# BI4.net
KiCad netlist of a schematic drawn in Altium Designer
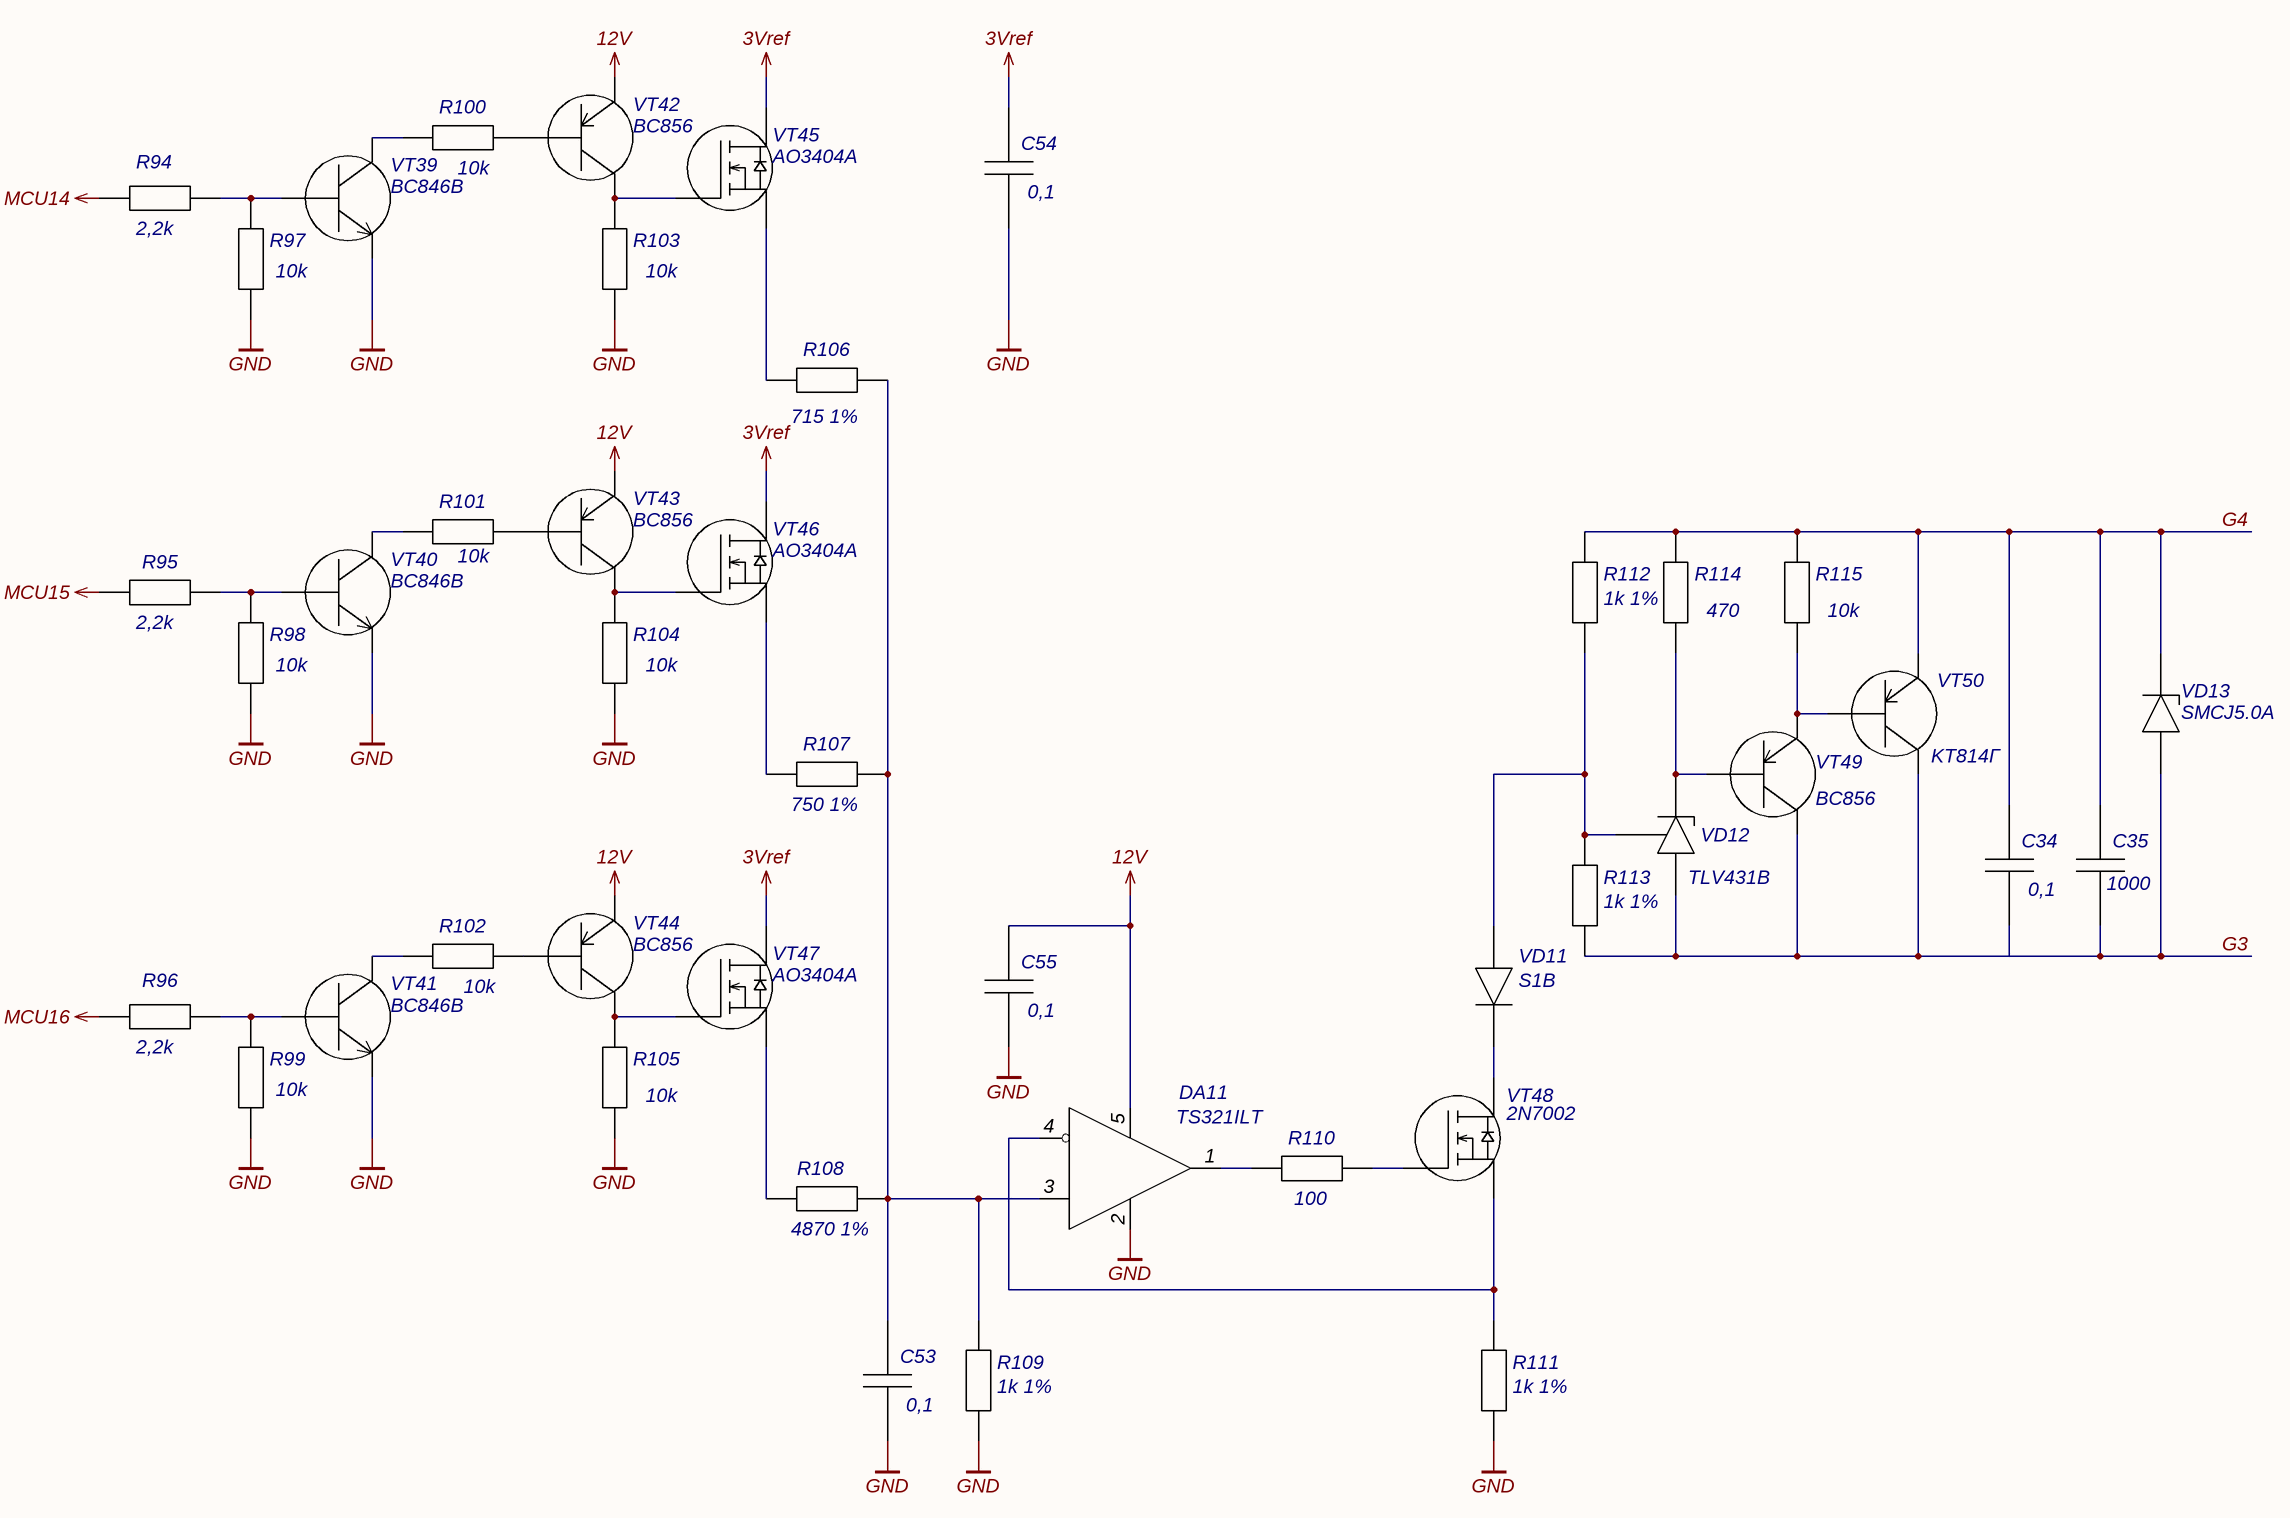
[diagram p0: BI4.SchDoc]

(export (version "E")
  (design (tool "Eeschema 10.0.6"))
  (components
    (comp (ref "C34")
      (value "0,1")
      (footprint "C0603")
      (description "Чип-конденсатор")
      (libsource (lib "Passive") (part "Chip Capasitor"))
    )
    (comp (ref "C35")
      (value "1000")
      (footprint "C0603")
      (description "Чип-конденсатор")
      (libsource (lib "Passive") (part "Chip Capasitor"))
    )
    (comp (ref "C53")
      (value "0,1")
      (footprint "C0603")
      (description "Чип-конденсатор")
      (libsource (lib "Passive") (part "Chip Capasitor"))
    )
    (comp (ref "C54")
      (value "0,1")
      (footprint "C0603")
      (description "Чип-конденсатор")
      (libsource (lib "Passive") (part "Chip Capasitor"))
    )
    (comp (ref "C55")
      (value "0,1")
      (footprint "C0603")
      (description "Чип-конденсатор")
      (libsource (lib "Passive") (part "Chip Capasitor"))
    )
    (comp (ref "DA11")
      (value "TS321ILT")
      (footprint "SOT-23-5")
      (description "1х Операционный усилитель")
      (libsource (lib "Schlib") (part "TS321ILT"))
    )
    (comp (ref "R94")
      (value "2,2k")
      (footprint "R0603")
      (description "Чип-резистор")
      (libsource (lib "Passive") (part "Chip Resistor"))
    )
    (comp (ref "R95")
      (value "2,2k")
      (footprint "R0603")
      (description "Чип-резистор")
      (libsource (lib "Passive") (part "Chip Resistor"))
    )
    (comp (ref "R96")
      (value "2,2k")
      (footprint "R0603")
      (description "Чип-резистор")
      (libsource (lib "Passive") (part "Chip Resistor"))
    )
    (comp (ref "R97")
      (value "10k")
      (footprint "R0603")
      (description "Чип-резистор")
      (libsource (lib "") (part "Chip Resistor_1"))
    )
    (comp (ref "R98")
      (value "10k")
      (footprint "R0603")
      (description "Чип-резистор")
      (libsource (lib "") (part "Chip Resistor_1"))
    )
    (comp (ref "R99")
      (value "10k")
      (footprint "R0603")
      (description "Чип-резистор")
      (libsource (lib "") (part "Chip Resistor_1"))
    )
    (comp (ref "R100")
      (value "10k")
      (footprint "R0603")
      (description "Чип-резистор")
      (libsource (lib "Passive") (part "Chip Resistor"))
    )
    (comp (ref "R101")
      (value "10k")
      (footprint "R0603")
      (description "Чип-резистор")
      (libsource (lib "Passive") (part "Chip Resistor"))
    )
    (comp (ref "R102")
      (value "10k")
      (footprint "R0603")
      (description "Чип-резистор")
      (libsource (lib "Passive") (part "Chip Resistor"))
    )
    (comp (ref "R103")
      (value "10k")
      (footprint "R0603")
      (description "Чип-резистор")
      (libsource (lib "") (part "Chip Resistor_1"))
    )
    (comp (ref "R104")
      (value "10k")
      (footprint "R0603")
      (description "Чип-резистор")
      (libsource (lib "") (part "Chip Resistor_1"))
    )
    (comp (ref "R105")
      (value "10k")
      (footprint "R0603")
      (description "Чип-резистор")
      (libsource (lib "") (part "Chip Resistor_1"))
    )
    (comp (ref "R106")
      (value "715 1%")
      (footprint "R0603")
      (description "Чип-резистор")
      (fields (field (name "PARTNUMBER") "RC0603FR-07715RL"))
      (libsource (lib "Passive") (part "Chip Resistor"))
    )
    (comp (ref "R107")
      (value "750 1%")
      (footprint "R0603")
      (description "Чип-резистор")
      (fields (field (name "PARTNUMBER") "RC0603FR-07750RL"))
      (libsource (lib "Passive") (part "Chip Resistor"))
    )
    (comp (ref "R108")
      (value "4870 1%")
      (footprint "R0603")
      (description "Чип-резистор")
      (fields (field (name "PARTNUMBER") "RC0603FR-074K87L"))
      (libsource (lib "Passive") (part "Chip Resistor"))
    )
    (comp (ref "R109")
      (value "1k 1%")
      (footprint "R0603")
      (description "Чип-резистор")
      (fields (field (name "PARTNUMBER") "CRCW06031K00FKEAC"))
      (libsource (lib "") (part "Chip Resistor_1"))
    )
    (comp (ref "R110")
      (value "100")
      (footprint "R0603")
      (description "Чип-резистор")
      (libsource (lib "Passive") (part "Chip Resistor"))
    )
    (comp (ref "R111")
      (value "1k 1%")
      (footprint "R0603")
      (description "Чип-резистор")
      (fields (field (name "PARTNUMBER") "CRCW06031K00FKEAC"))
      (libsource (lib "") (part "Chip Resistor_1"))
    )
    (comp (ref "R112")
      (value "1k 1%")
      (footprint "R0603")
      (description "Чип-резистор")
      (fields (field (name "PARTNUMBER") "CRCW06031K00FKEAC"))
      (libsource (lib "") (part "Chip Resistor_1"))
    )
    (comp (ref "R113")
      (value "1k 1%")
      (footprint "R0603")
      (description "Чип-резистор")
      (fields (field (name "PARTNUMBER") "CRCW06031K00FKEAC"))
      (libsource (lib "") (part "Chip Resistor_1"))
    )
    (comp (ref "R114")
      (value "470")
      (footprint "R0603")
      (description "Чип-резистор")
      (libsource (lib "") (part "Chip Resistor_1"))
    )
    (comp (ref "R115")
      (value "10k")
      (footprint "R0603")
      (description "Чип-резистор")
      (libsource (lib "") (part "Chip Resistor_1"))
    )
    (comp (ref "VD11")
      (value "S1B")
      (footprint "DO-214AC")
      (description "Диод выпрямительный, 100В")
      (fields (field (name "MANUFACTURER") "Diotec Semiconductor"))
      (libsource (lib "Schlib") (part "S1B"))
    )
    (comp (ref "VD12")
      (value "TLV431B")
      (footprint "SOT-23")
      (description "Стабилитрон регулируемый, 6В")
      (fields (field (name "MANUFACTURER") "Texas Instruments"))
      (libsource (lib "Schlib") (part "TLV431B"))
    )
    (comp (ref "VD13")
      (value "SMCJ5.0A")
      (footprint "DO-214AB")
      (description "Защитный диод, 5В")
      (fields (field (name "MANUFACTURER") "UTD Semiconductor Co.,Ltd"))
      (libsource (lib "Schlib") (part "SMCJ5.0A"))
    )
    (comp (ref "VT39")
      (value "BC846B")
      (footprint "SOT-23")
      (description "Транзистор биполярный NPN, 65В")
      (fields (field (name "MANUFACTURER") "Nexperia B.V."))
      (libsource (lib "Schlib") (part "BC846B"))
    )
    (comp (ref "VT40")
      (value "BC846B")
      (footprint "SOT-23")
      (description "Транзистор биполярный NPN, 65В")
      (fields (field (name "MANUFACTURER") "Nexperia B.V."))
      (libsource (lib "Schlib") (part "BC846B"))
    )
    (comp (ref "VT41")
      (value "BC846B")
      (footprint "SOT-23")
      (description "Транзистор биполярный NPN, 65В")
      (fields (field (name "MANUFACTURER") "Nexperia B.V."))
      (libsource (lib "Schlib") (part "BC846B"))
    )
    (comp (ref "VT42")
      (value "BC856")
      (footprint "SOT-23")
      (description "Транзистор биполярный PNP, 65В")
      (fields (field (name "MANUFACTURER") "Nexperia"))
      (libsource (lib "Schlib") (part "BC856"))
    )
    (comp (ref "VT43")
      (value "BC856")
      (footprint "SOT-23")
      (description "Транзистор биполярный PNP, 65В")
      (fields (field (name "MANUFACTURER") "Nexperia"))
      (libsource (lib "Schlib") (part "BC856"))
    )
    (comp (ref "VT44")
      (value "BC856")
      (footprint "SOT-23")
      (description "Транзистор биполярный PNP, 65В")
      (fields (field (name "MANUFACTURER") "Nexperia"))
      (libsource (lib "Schlib") (part "BC856"))
    )
    (comp (ref "VT45")
      (value "AO3404A")
      (footprint "SOT-23")
      (description "Транзистор MOSFET N-канал, 30В")
      (fields (field (name "MANUFACTURER") "UTD Semiconductor Co.,Ltd"))
      (libsource (lib "Schlib") (part "AO3404A"))
    )
    (comp (ref "VT46")
      (value "AO3404A")
      (footprint "SOT-23")
      (description "Транзистор MOSFET N-канал, 30В")
      (fields (field (name "MANUFACTURER") "UTD Semiconductor Co.,Ltd"))
      (libsource (lib "Schlib") (part "AO3404A"))
    )
    (comp (ref "VT47")
      (value "AO3404A")
      (footprint "SOT-23")
      (description "Транзистор MOSFET N-канал, 30В")
      (fields (field (name "MANUFACTURER") "UTD Semiconductor Co.,Ltd"))
      (libsource (lib "Schlib") (part "AO3404A"))
    )
    (comp (ref "VT48")
      (value "2N7002")
      (footprint "SOT-23")
      (description "Транзистор MOSFET N-канал, 60В")
      (fields (field (name "MANUFACTURER") "UTD Semiconductor Co."))
      (libsource (lib "Schlib") (part "2N7002"))
    )
    (comp (ref "VT49")
      (value "BC856")
      (footprint "SOT-23")
      (description "Транзистор биполярный PNP, 65В")
      (fields (field (name "MANUFACTURER") "Nexperia"))
      (libsource (lib "Schlib") (part "BC856"))
    )
    (comp (ref "VT50")
      (value "KT814Г")
      (footprint "TO-126")
      (description "Транзистор биполярный PNP, 100В")
      (fields (field (name "MANUFACTURER") "АО «ГРУППА КРЕМНИЙ ЭЛ»"))
      (libsource (lib "Schlib") (part "KT814Г"))
    )
  )
  (nets
    (net (code "1") (name "/G3") (class "Default")
      (node (ref "C34") (pin "1") (pinfunction "1_1") (pintype "passive"))
      (node (ref "C35") (pin "1") (pinfunction "1_1") (pintype "passive"))
      (node (ref "R113") (pin "1") (pinfunction "1_1") (pintype "passive"))
      (node (ref "VD12") (pin "1") (pinfunction "1_1") (pintype "passive"))
      (node (ref "VD13") (pin "1") (pinfunction "1_1") (pintype "passive"))
      (node (ref "VT49") (pin "2") (pinfunction "2_2") (pintype "passive"))
      (node (ref "VT50") (pin "2") (pinfunction "2_2") (pintype "passive"))
    )
    (net (code "2") (name "/G4") (class "Default")
      (node (ref "C34") (pin "2") (pinfunction "2_2") (pintype "passive"))
      (node (ref "C35") (pin "2") (pinfunction "2_2") (pintype "passive"))
      (node (ref "R112") (pin "2") (pinfunction "2_2") (pintype "passive"))
      (node (ref "R114") (pin "2") (pinfunction "2_2") (pintype "passive"))
      (node (ref "R115") (pin "2") (pinfunction "2_2") (pintype "passive"))
      (node (ref "VD13") (pin "2") (pinfunction "2_2") (pintype "passive"))
      (node (ref "VT50") (pin "1") (pinfunction "1_1") (pintype "passive"))
    )
    (net (code "3") (name "3Vref") (class "Default")
      (node (ref "C54") (pin "2") (pinfunction "2_2") (pintype "passive"))
      (node (ref "VT45") (pin "2") (pinfunction "D_2") (pintype "passive"))
      (node (ref "VT46") (pin "2") (pinfunction "D_2") (pintype "passive"))
      (node (ref "VT47") (pin "2") (pinfunction "D_2") (pintype "passive"))
    )
    (net (code "4") (name "12V") (class "Default")
      (node (ref "C55") (pin "2") (pinfunction "2_2") (pintype "passive"))
      (node (ref "DA11") (pin "5") (pinfunction "Vcc_5") (pintype "passive"))
      (node (ref "VT42") (pin "1") (pinfunction "1_1") (pintype "passive"))
      (node (ref "VT43") (pin "1") (pinfunction "1_1") (pintype "passive"))
      (node (ref "VT44") (pin "1") (pinfunction "1_1") (pintype "passive"))
    )
    (net (code "5") (name "GND") (class "Default")
      (node (ref "C53") (pin "1") (pinfunction "1_1") (pintype "passive"))
      (node (ref "C54") (pin "1") (pinfunction "1_1") (pintype "passive"))
      (node (ref "C55") (pin "1") (pinfunction "1_1") (pintype "passive"))
      (node (ref "DA11") (pin "2") (pinfunction "GND_2") (pintype "passive"))
      (node (ref "R103") (pin "1") (pinfunction "1_1") (pintype "passive"))
      (node (ref "R104") (pin "1") (pinfunction "1_1") (pintype "passive"))
      (node (ref "R105") (pin "1") (pinfunction "1_1") (pintype "passive"))
      (node (ref "R109") (pin "1") (pinfunction "1_1") (pintype "passive"))
      (node (ref "R111") (pin "1") (pinfunction "1_1") (pintype "passive"))
      (node (ref "R97") (pin "1") (pinfunction "1_1") (pintype "passive"))
      (node (ref "R98") (pin "1") (pinfunction "1_1") (pintype "passive"))
      (node (ref "R99") (pin "1") (pinfunction "1_1") (pintype "passive"))
      (node (ref "VT39") (pin "2") (pinfunction "E_2") (pintype "passive"))
      (node (ref "VT40") (pin "2") (pinfunction "E_2") (pintype "passive"))
      (node (ref "VT41") (pin "2") (pinfunction "E_2") (pintype "passive"))
    )
    (net (code "6") (name "MCU14") (class "Default")
      (node (ref "R94") (pin "1") (pinfunction "1_1") (pintype "passive"))
    )
    (net (code "7") (name "MCU15") (class "Default")
      (node (ref "R95") (pin "1") (pinfunction "1_1") (pintype "passive"))
    )
    (net (code "8") (name "MCU16") (class "Default")
      (node (ref "R96") (pin "1") (pinfunction "1_1") (pintype "passive"))
    )
    (net (code "9") (name "Net-(DA11-+)") (class "Default")
      (node (ref "C53") (pin "2") (pinfunction "2_2") (pintype "passive"))
      (node (ref "DA11") (pin "3") (pinfunction "+_3") (pintype "passive"))
      (node (ref "R106") (pin "2") (pinfunction "2_2") (pintype "passive"))
      (node (ref "R107") (pin "2") (pinfunction "2_2") (pintype "passive"))
      (node (ref "R108") (pin "2") (pinfunction "2_2") (pintype "passive"))
      (node (ref "R109") (pin "2") (pinfunction "2_2") (pintype "passive"))
    )
    (net (code "10") (name "Net-(DA11--)") (class "Default")
      (node (ref "DA11") (pin "4") (pinfunction "-_4") (pintype "passive"))
      (node (ref "R111") (pin "2") (pinfunction "2_2") (pintype "passive"))
      (node (ref "VT48") (pin "3") (pinfunction "S_3") (pintype "passive"))
    )
    (net (code "11") (name "Net-(DA11-OUT)") (class "Default")
      (node (ref "DA11") (pin "1") (pinfunction "OUT_1") (pintype "passive"))
      (node (ref "R110") (pin "1") (pinfunction "1_1") (pintype "passive"))
    )
    (net (code "12") (name "Net-(R100-Pad2)") (class "Default")
      (node (ref "R100") (pin "2") (pinfunction "2_2") (pintype "passive"))
      (node (ref "VT42") (pin "3") (pinfunction "3_3") (pintype "passive"))
    )
    (net (code "13") (name "Net-(R101-Pad2)") (class "Default")
      (node (ref "R101") (pin "2") (pinfunction "2_2") (pintype "passive"))
      (node (ref "VT43") (pin "3") (pinfunction "3_3") (pintype "passive"))
    )
    (net (code "14") (name "Net-(R102-Pad2)") (class "Default")
      (node (ref "R102") (pin "2") (pinfunction "2_2") (pintype "passive"))
      (node (ref "VT44") (pin "3") (pinfunction "3_3") (pintype "passive"))
    )
    (net (code "15") (name "Net-(R112-Pad1)") (class "Default")
      (node (ref "R112") (pin "1") (pinfunction "1_1") (pintype "passive"))
      (node (ref "R113") (pin "2") (pinfunction "2_2") (pintype "passive"))
      (node (ref "VD11") (pin "1") (pinfunction "1_1") (pintype "passive"))
      (node (ref "VD12") (pin "3") (pinfunction "3_3") (pintype "passive"))
    )
    (net (code "16") (name "Net-(R114-Pad1)") (class "Default")
      (node (ref "R114") (pin "1") (pinfunction "1_1") (pintype "passive"))
      (node (ref "VD12") (pin "2") (pinfunction "2_2") (pintype "passive"))
      (node (ref "VT49") (pin "3") (pinfunction "3_3") (pintype "passive"))
    )
    (net (code "17") (name "Net-(R115-Pad1)") (class "Default")
      (node (ref "R115") (pin "1") (pinfunction "1_1") (pintype "passive"))
      (node (ref "VT49") (pin "1") (pinfunction "1_1") (pintype "passive"))
      (node (ref "VT50") (pin "3") (pinfunction "3_3") (pintype "passive"))
    )
    (net (code "18") (name "Net-(VT39-B)") (class "Default")
      (node (ref "R94") (pin "2") (pinfunction "2_2") (pintype "passive"))
      (node (ref "R97") (pin "2") (pinfunction "2_2") (pintype "passive"))
      (node (ref "VT39") (pin "1") (pinfunction "B_1") (pintype "passive"))
    )
    (net (code "19") (name "Net-(VT39-C)") (class "Default")
      (node (ref "R100") (pin "1") (pinfunction "1_1") (pintype "passive"))
      (node (ref "VT39") (pin "3") (pinfunction "C_3") (pintype "passive"))
    )
    (net (code "20") (name "Net-(VT40-B)") (class "Default")
      (node (ref "R95") (pin "2") (pinfunction "2_2") (pintype "passive"))
      (node (ref "R98") (pin "2") (pinfunction "2_2") (pintype "passive"))
      (node (ref "VT40") (pin "1") (pinfunction "B_1") (pintype "passive"))
    )
    (net (code "21") (name "Net-(VT40-C)") (class "Default")
      (node (ref "R101") (pin "1") (pinfunction "1_1") (pintype "passive"))
      (node (ref "VT40") (pin "3") (pinfunction "C_3") (pintype "passive"))
    )
    (net (code "22") (name "Net-(VT41-B)") (class "Default")
      (node (ref "R96") (pin "2") (pinfunction "2_2") (pintype "passive"))
      (node (ref "R99") (pin "2") (pinfunction "2_2") (pintype "passive"))
      (node (ref "VT41") (pin "1") (pinfunction "B_1") (pintype "passive"))
    )
    (net (code "23") (name "Net-(VT41-C)") (class "Default")
      (node (ref "R102") (pin "1") (pinfunction "1_1") (pintype "passive"))
      (node (ref "VT41") (pin "3") (pinfunction "C_3") (pintype "passive"))
    )
    (net (code "24") (name "Net-(VT45-G)") (class "Default")
      (node (ref "R103") (pin "2") (pinfunction "2_2") (pintype "passive"))
      (node (ref "VT42") (pin "2") (pinfunction "2_2") (pintype "passive"))
      (node (ref "VT45") (pin "1") (pinfunction "G_1") (pintype "passive"))
    )
    (net (code "25") (name "Net-(VT45-S)") (class "Default")
      (node (ref "R106") (pin "1") (pinfunction "1_1") (pintype "passive"))
      (node (ref "VT45") (pin "3") (pinfunction "S_3") (pintype "passive"))
    )
    (net (code "26") (name "Net-(VT46-G)") (class "Default")
      (node (ref "R104") (pin "2") (pinfunction "2_2") (pintype "passive"))
      (node (ref "VT43") (pin "2") (pinfunction "2_2") (pintype "passive"))
      (node (ref "VT46") (pin "1") (pinfunction "G_1") (pintype "passive"))
    )
    (net (code "27") (name "Net-(VT46-S)") (class "Default")
      (node (ref "R107") (pin "1") (pinfunction "1_1") (pintype "passive"))
      (node (ref "VT46") (pin "3") (pinfunction "S_3") (pintype "passive"))
    )
    (net (code "28") (name "Net-(VT47-G)") (class "Default")
      (node (ref "R105") (pin "2") (pinfunction "2_2") (pintype "passive"))
      (node (ref "VT44") (pin "2") (pinfunction "2_2") (pintype "passive"))
      (node (ref "VT47") (pin "1") (pinfunction "G_1") (pintype "passive"))
    )
    (net (code "29") (name "Net-(VT47-S)") (class "Default")
      (node (ref "R108") (pin "1") (pinfunction "1_1") (pintype "passive"))
      (node (ref "VT47") (pin "3") (pinfunction "S_3") (pintype "passive"))
    )
    (net (code "30") (name "Net-(VT48-D)") (class "Default")
      (node (ref "VD11") (pin "2") (pinfunction "2_2") (pintype "passive"))
      (node (ref "VT48") (pin "2") (pinfunction "D_2") (pintype "passive"))
    )
    (net (code "31") (name "Net-(VT48-G)") (class "Default")
      (node (ref "R110") (pin "2") (pinfunction "2_2") (pintype "passive"))
      (node (ref "VT48") (pin "1") (pinfunction "G_1") (pintype "passive"))
    )
  )
)
